# controlPanel.net
KiCad netlist of a schematic drawn in EAGLE
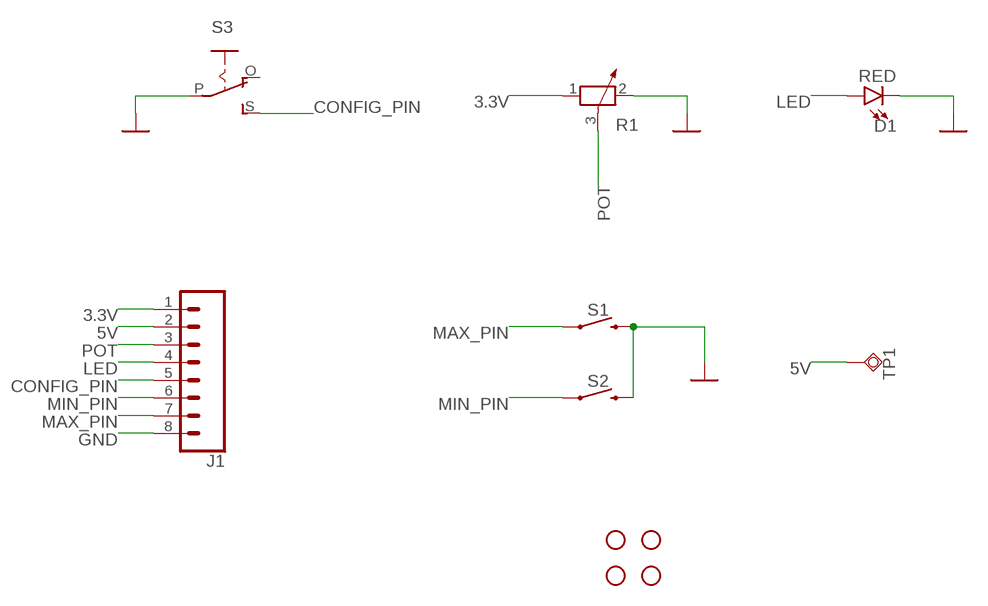
[diagram p0: schematic, sheet 1]

(export (version "E")
  (design (tool "Eeschema 10.0.6"))
  (components
    (comp (ref "D1")
      (value "RED")
      (footprint "eagle-import:SPARKFUN-LED_LED-0603")
      (libsource (lib "eagle-import") (part "SPARKFUN-LED_LED-RED0603"))
    )
    (comp (ref "H1")
      (value "STAND-OFFTIGHT")
      (footprint "eagle-import:STAND-OFF-TIGHT")
      (libsource (lib "eagle-import") (part "STAND-OFFTIGHT"))
    )
    (comp (ref "H2")
      (value "STAND-OFFTIGHT")
      (footprint "eagle-import:STAND-OFF-TIGHT")
      (libsource (lib "eagle-import") (part "STAND-OFFTIGHT"))
    )
    (comp (ref "H3")
      (value "STAND-OFFTIGHT")
      (footprint "eagle-import:STAND-OFF-TIGHT")
      (libsource (lib "eagle-import") (part "STAND-OFFTIGHT"))
    )
    (comp (ref "H4")
      (value "STAND-OFFTIGHT")
      (footprint "eagle-import:STAND-OFF-TIGHT")
      (libsource (lib "eagle-import") (part "STAND-OFFTIGHT"))
    )
    (comp (ref "J1")
      (value "CONN_08SMD-COMBO-FEMALE")
      (footprint "eagle-import:1X08_SMD_COMBINED")
      (libsource (lib "eagle-import") (part "CONN_08SMD-COMBO-FEMALE"))
    )
    (comp (ref "R1")
      (value "RCL_POTENTIOMETER_PT-10")
      (footprint "eagle-import:RCL_PT-10")
      (libsource (lib "eagle-import") (part "RCL_POTENTIOMETER_PT-10"))
    )
    (comp (ref "S1")
      (value "SPARKFUN-SWITCHES_MOMENTARY-SWITCH-SPST-PTH-12MM")
      (footprint "eagle-import:SPARKFUN-SWITCHES_TACTILE_SWITCH_PTH_12MM")
      (libsource (lib "eagle-import") (part "SPARKFUN-SWITCHES_MOMENTARY-SWITCH-SPST-PTH-12MM"))
    )
    (comp (ref "S2")
      (value "SPARKFUN-SWITCHES_MOMENTARY-SWITCH-SPST-PTH-12MM")
      (footprint "eagle-import:SPARKFUN-SWITCHES_TACTILE_SWITCH_PTH_12MM")
      (libsource (lib "eagle-import") (part "SPARKFUN-SWITCHES_MOMENTARY-SWITCH-SPST-PTH-12MM"))
    )
    (comp (ref "S3")
      (value "ADAFRUIT_EG1218S")
      (footprint "eagle-import:ADAFRUIT_EG1218")
      (libsource (lib "eagle-import") (part "ADAFRUIT_EG1218S"))
    )
    (comp (ref "TP1")
      (value "TESTPAD_TPSQTP20R")
      (footprint "eagle-import:TESTPAD_TP20R")
      (libsource (lib "eagle-import") (part "TESTPAD_TPSQTP20R"))
    )
  )
  (nets
    (net (code "1") (name "/3.3V") (class "Default")
      (node (ref "J1") (pin "1") (pinfunction "1_1") (pintype "passive"))
      (node (ref "R1") (pin "1") (pinfunction "1_1") (pintype "passive"))
    )
    (net (code "2") (name "/5V") (class "Default")
      (node (ref "J1") (pin "2") (pinfunction "2_2") (pintype "passive"))
      (node (ref "TP1") (pin "TP") (pinfunction "TP_TP") (pintype "input"))
    )
    (net (code "3") (name "/CONFIG_PIN") (class "Default")
      (node (ref "J1") (pin "5") (pinfunction "5_5") (pintype "passive"))
      (node (ref "S3") (pin "S") (pinfunction "S_S") (pintype "passive"))
    )
    (net (code "4") (name "/LED") (class "Default")
      (node (ref "D1") (pin "A") (pinfunction "A_A") (pintype "passive"))
      (node (ref "J1") (pin "4") (pinfunction "4_4") (pintype "passive"))
    )
    (net (code "5") (name "/MAX_PIN") (class "Default")
      (node (ref "J1") (pin "7") (pinfunction "7_7") (pintype "passive"))
      (node (ref "S1") (pin "1") (pinfunction "1_1") (pintype "passive"))
    )
    (net (code "6") (name "/MIN_PIN") (class "Default")
      (node (ref "J1") (pin "6") (pinfunction "6_6") (pintype "passive"))
      (node (ref "S2") (pin "1") (pinfunction "1_1") (pintype "passive"))
    )
    (net (code "7") (name "/POT") (class "Default")
      (node (ref "J1") (pin "3") (pinfunction "3_3") (pintype "passive"))
      (node (ref "R1") (pin "3") (pinfunction "3_3") (pintype "passive"))
    )
    (net (code "8") (name "3-5-PIN-SMD_GND") (class "Default")
      (node (ref "D1") (pin "C") (pinfunction "C_C") (pintype "passive"))
      (node (ref "J1") (pin "8") (pinfunction "8_8") (pintype "passive"))
      (node (ref "R1") (pin "2") (pinfunction "2_2") (pintype "passive"))
      (node (ref "S1") (pin "3") (pinfunction "2_3") (pintype "passive"))
      (node (ref "S2") (pin "3") (pinfunction "2_3") (pintype "passive"))
      (node (ref "S3") (pin "P") (pinfunction "P_P") (pintype "passive"))
    )
    (net (code "9") (name "unconnected-(S3-PadO)") (class "Default")
      (node (ref "S3") (pin "O") (pinfunction "O_O") (pintype "passive"))
    )
  )
)
